# 5V_to_3V3.net
KiCad netlist of a schematic drawn in Altium Designer
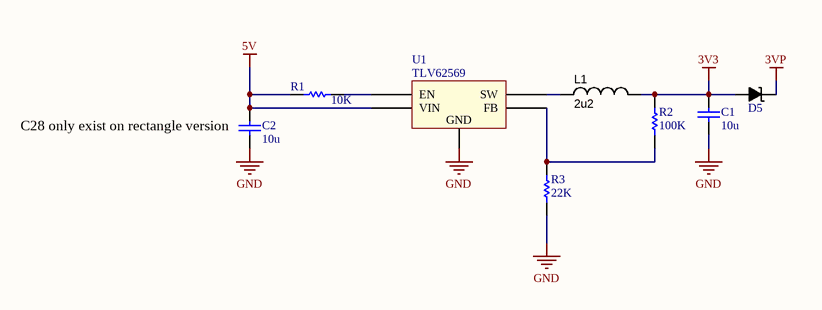
[diagram p0: 5V_to_3V3.SchDoc]

(export (version "E")
  (design (tool "Eeschema 10.0.6"))
  (components
    (comp (ref "C1")
      (value "10u")
      (footprint "CAPC2012X135N")
      (description "Capacitor")
      (fields (field (name "Comment") "Cap") (field (name "PUBLISHER") "Altium Limited"))
      (libsource (lib "IOBoard_Low") (part "Cap"))
    )
    (comp (ref "C2")
      (value "10u")
      (footprint "CAPC2012X135N")
      (description "Capacitor")
      (fields (field (name "Comment") "Cap") (field (name "PUBLISHER") "Altium Limited"))
      (libsource (lib "IOBoard_Low") (part "Cap"))
    )
    (comp (ref "D5")
      (value "SS24")
      (footprint "DO-214AA")
      (description "2.0A SURFACE MOUNT SCHOTTKY BARRIER RECTIFIER")
      (fields (field (name "VOLTAGE") "40V"))
      (libsource (lib "IOBoard_Low") (part "SS24"))
    )
    (comp (ref "L1")
      (value "2u2")
      (footprint "INDM3225X240N")
      (description "IHLP SMD 4040")
      (fields (field (name "Comment") "inductor"))
      (libsource (lib "IOBoard_Low") (part "INDC"))
    )
    (comp (ref "R1")
      (value "10K")
      (footprint "RESC1608X55N")
      (description "Resistor")
      (fields (field (name "Comment") "Res1") (field (name "PUBLISHER") "Altium Limited"))
      (libsource (lib "IOBoard_Low") (part "Res1"))
    )
    (comp (ref "R2")
      (value "100K")
      (footprint "RESC2012X70N")
      (description "Resistor")
      (fields (field (name "Comment") "Res1") (field (name "PUBLISHER") "Altium Limited"))
      (libsource (lib "IOBoard_Low") (part "Res1"))
    )
    (comp (ref "R3")
      (value "22K")
      (footprint "RESC2012X70N")
      (description "Resistor")
      (fields (field (name "Comment") "Res1") (field (name "PUBLISHER") "Altium Limited"))
      (libsource (lib "IOBoard_Low") (part "Res1"))
    )
    (comp (ref "U1")
      (value "TLV62569")
      (footprint "SOT23-5")
      (description "2-A High Efficiency Synchronous Buck Converter in SOT Package")
      (fields (field (name "MANUFACTURER") "TI"))
      (libsource (lib "IOBoard") (part "TLV62569"))
    )
  )
  (nets
    (net (code "1") (name "3V3") (class "Default")
      (node (ref "C1") (pin "2") (pinfunction "2_2") (pintype "passive"))
      (node (ref "D5") (pin "A") (pinfunction "Anode_A") (pintype "passive"))
      (node (ref "L1") (pin "2") (pinfunction "2_2") (pintype "passive"))
      (node (ref "R2") (pin "2") (pinfunction "2_2") (pintype "passive"))
    )
    (net (code "2") (name "3VP") (class "Default")
      (node (ref "D5") (pin "K") (pinfunction "Cathode_K") (pintype "passive"))
    )
    (net (code "3") (name "5V") (class "Default")
      (node (ref "C2") (pin "2") (pinfunction "2_2") (pintype "passive"))
      (node (ref "R1") (pin "1") (pinfunction "1_1") (pintype "passive"))
      (node (ref "U1") (pin "4") (pinfunction "VIN_4") (pintype "passive"))
    )
    (net (code "4") (name "GND") (class "Default")
      (node (ref "C1") (pin "1") (pinfunction "1_1") (pintype "passive"))
      (node (ref "C2") (pin "1") (pinfunction "1_1") (pintype "passive"))
      (node (ref "R3") (pin "2") (pinfunction "2_2") (pintype "passive"))
      (node (ref "U1") (pin "2") (pinfunction "GND_2") (pintype "passive"))
    )
    (net (code "5") (name "Net-(U1-EN)") (class "Default")
      (node (ref "R1") (pin "2") (pinfunction "2_2") (pintype "passive"))
      (node (ref "U1") (pin "1") (pinfunction "EN_1") (pintype "passive"))
    )
    (net (code "6") (name "Net-(U1-FB)") (class "Default")
      (node (ref "R2") (pin "1") (pinfunction "1_1") (pintype "passive"))
      (node (ref "R3") (pin "1") (pinfunction "1_1") (pintype "passive"))
      (node (ref "U1") (pin "5") (pinfunction "FB_5") (pintype "passive"))
    )
    (net (code "7") (name "Net-(U1-SW)") (class "Default")
      (node (ref "L1") (pin "1") (pinfunction "1_1") (pintype "passive"))
      (node (ref "U1") (pin "3") (pinfunction "SW_3") (pintype "passive"))
    )
  )
)
